# Push_Button.net
KiCad netlist of a schematic drawn in Altium Designer
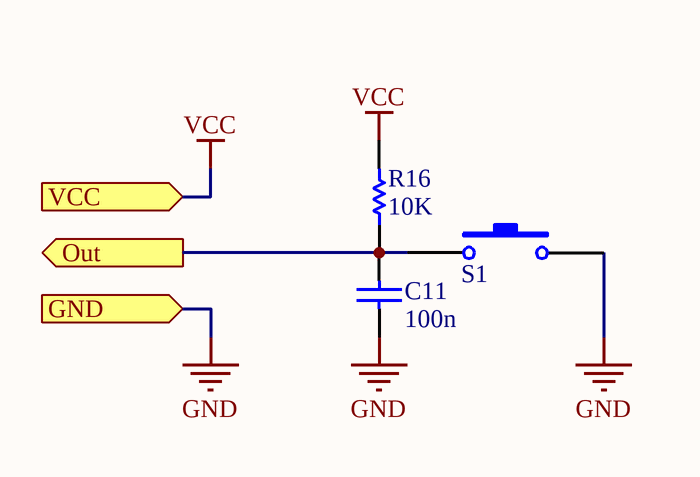
[diagram p0: Push_Button.SchDoc]

(export (version "E")
  (design (tool "Eeschema 10.0.6"))
  (components
    (comp (ref "C11")
      (value "100n")
      (footprint "CS-0603")
      (fields
        (field (name "TOLERANCE") "10%")
        (field (name "VOLTAGE") "16V")
        (field (name "Comment") "CS - CAPACITOR")
      )
      (libsource (lib "CHINOOK_LIBRARY") (part "CS - CAPACITOR"))
    )
    (comp (ref "R16")
      (value "10K")
      (footprint "RS-0603")
      (fields
        (field (name "TOLERANCE") "RES TOL")
        (field (name "POWER") "RES POWER")
        (field (name "Comment") "RS - RESISTOR")
      )
      (libsource (lib "CHINOOK_LIBRARY") (part "RS - RESISTOR"))
    )
    (comp (ref "S1")
      (value "SW - Tactile Switch")
      (footprint "SW-FSMSM")
      (libsource (lib "CHINOOK_LIBRARY") (part "SW - Tactile Switch"))
    )
  )
  (nets
    (net (code "1") (name "/Out") (class "Default")
      (node (ref "C11") (pin "2") (pinfunction "2_2") (pintype "passive"))
      (node (ref "R16") (pin "1") (pinfunction "1_1") (pintype "passive"))
      (node (ref "S1") (pin "1") (pinfunction "1_1") (pintype "passive"))
    )
    (net (code "2") (name "GND") (class "Default")
      (node (ref "C11") (pin "1") (pinfunction "1_1") (pintype "passive"))
      (node (ref "S1") (pin "2") (pinfunction "2_2") (pintype "passive"))
    )
    (net (code "3") (name "VCC") (class "Default")
      (node (ref "R16") (pin "2") (pinfunction "2_2") (pintype "passive"))
    )
  )
)
